# FMC_DIO_32ch_lvds_a.net
KiCad netlist of a schematic drawn in Altium Designer
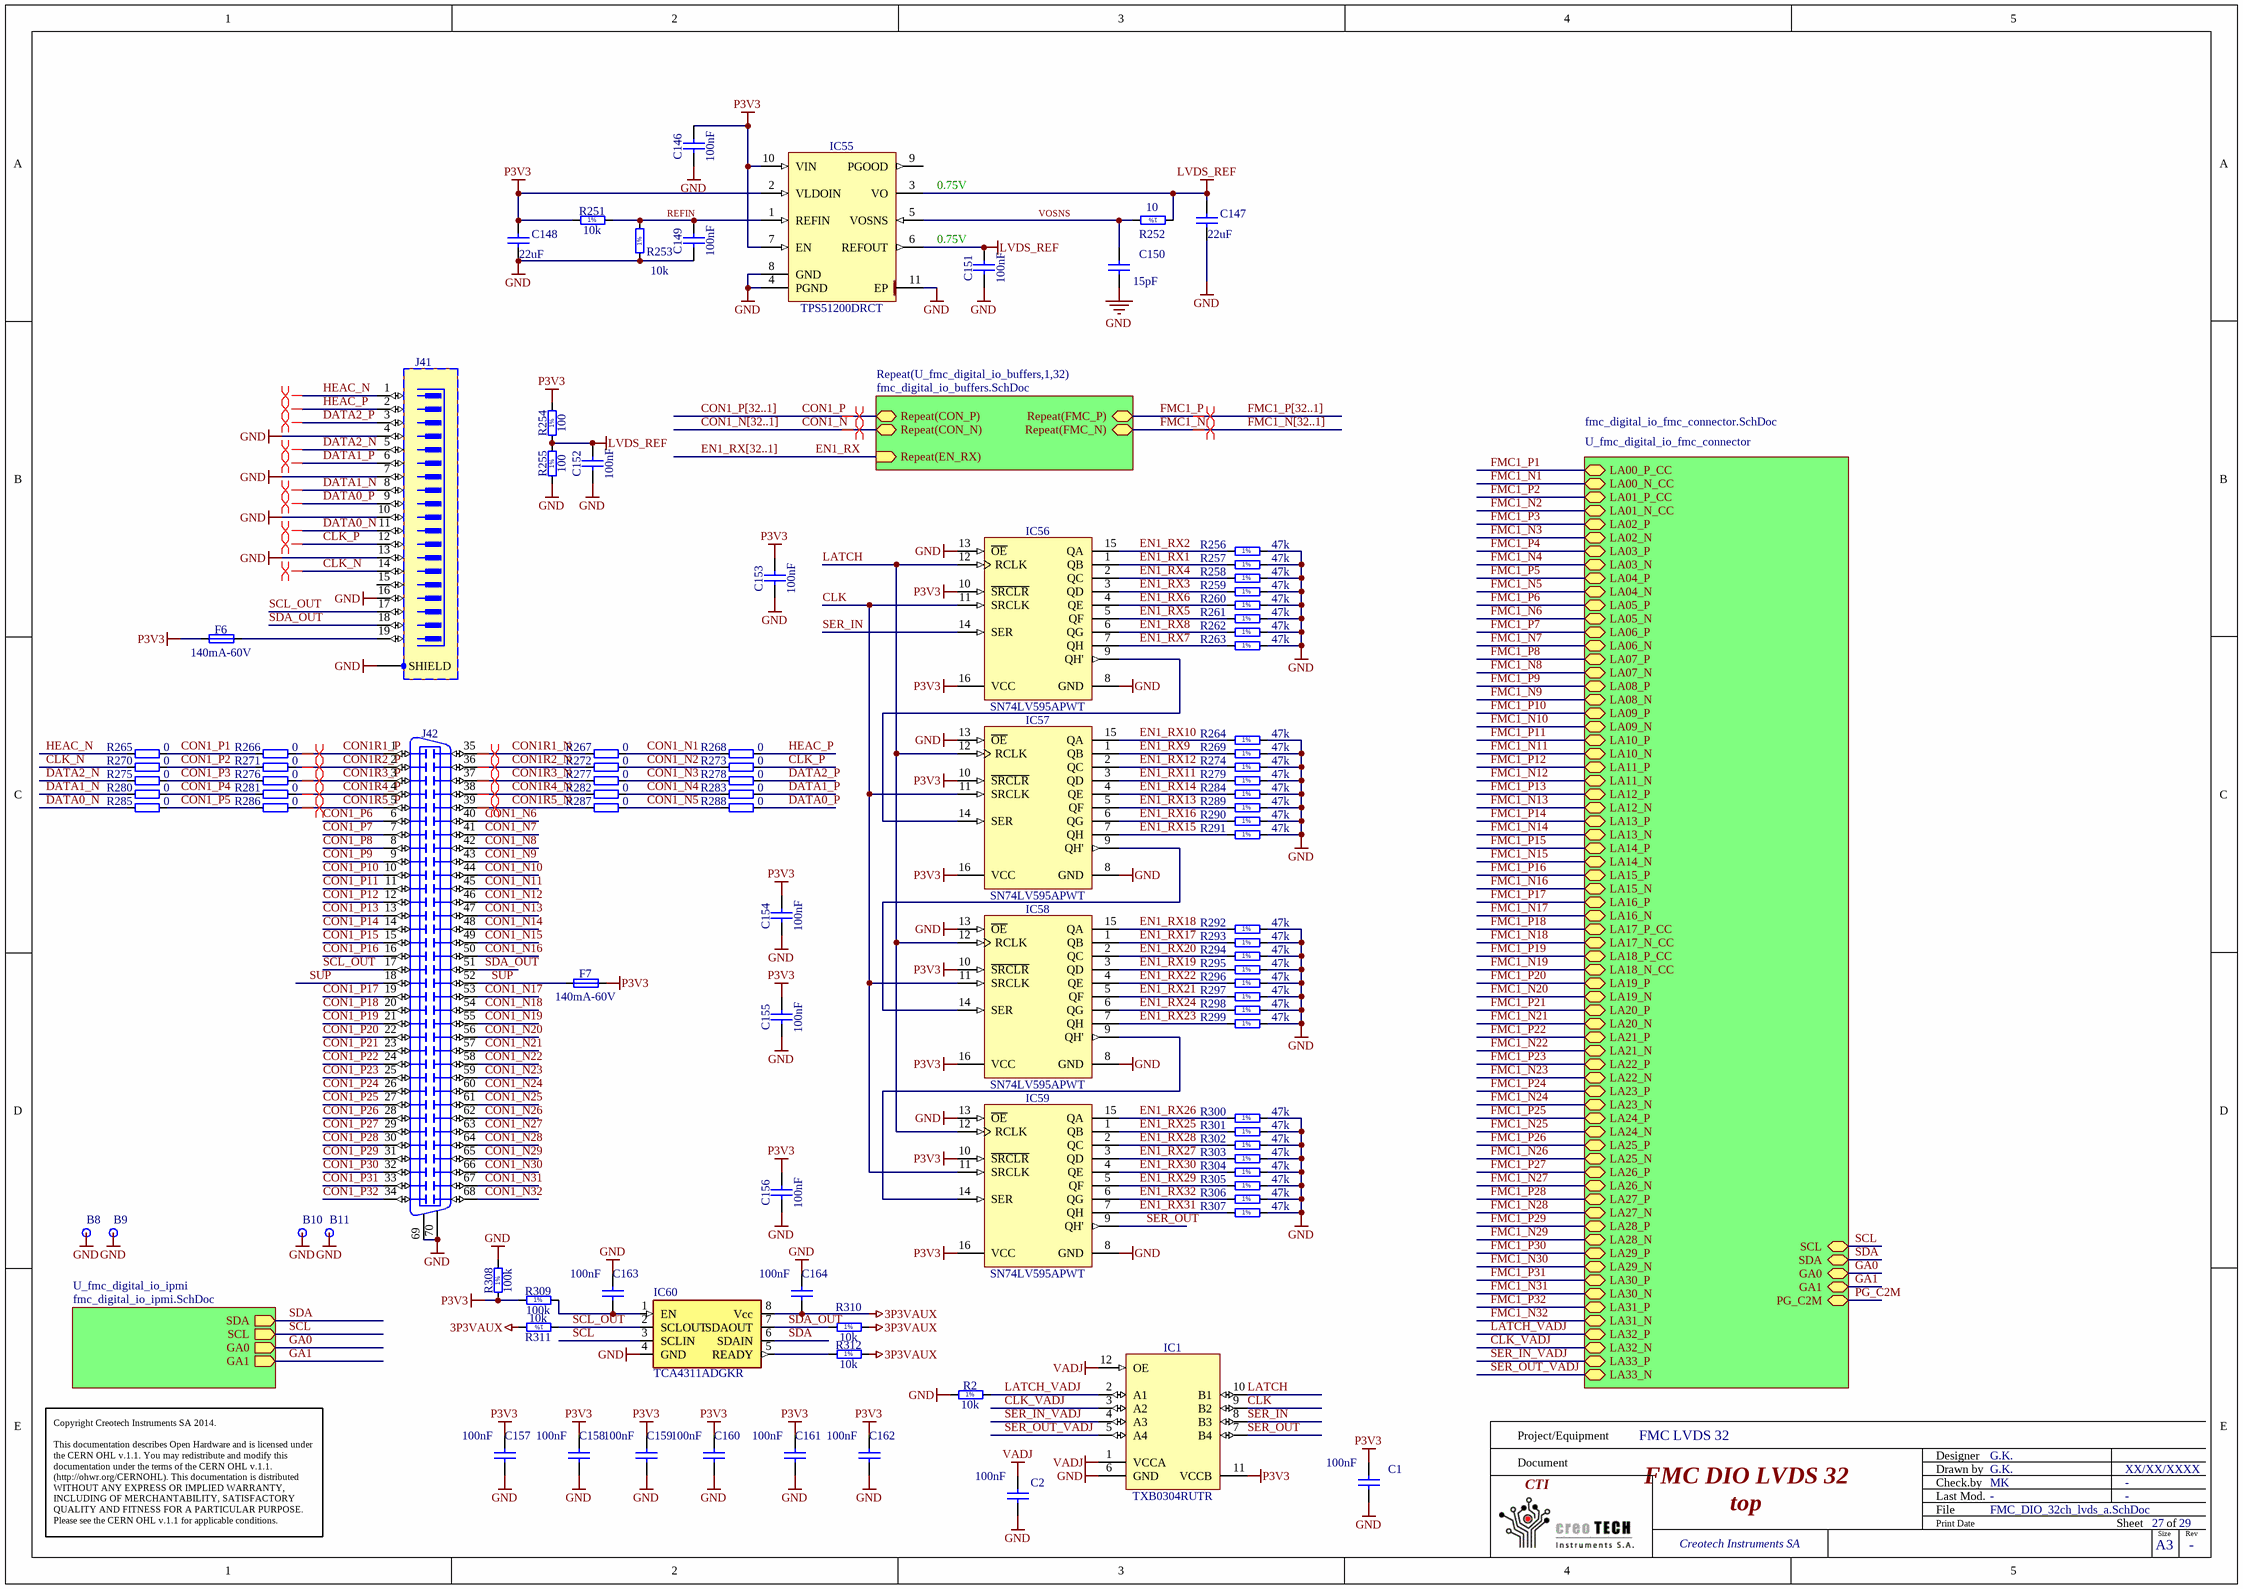
[diagram p0: FMC_DIO_32ch_lvds_a.SchDoc]

(export (version "E")
  (design (tool "Eeschema 10.0.6"))
  (components
    (comp (ref "B8")
      (value "Plated Hole")
      (footprint "MTG300_600")
      (description "Single Terminal Socket")
      (fields (field (name "PART NUMBER") "PLATED_HOLE3.0_PAD6.0") (field (name "AUTHOR") "CERN DEM JLC"))
      (libsource (lib "Eletro-mechanical") (part "Single Terminal Socket"))
    )
    (comp (ref "B9")
      (value "Plated Hole")
      (footprint "MTG300_600")
      (description "Single Terminal Socket")
      (fields (field (name "PART NUMBER") "PLATED_HOLE3.0_PAD6.0") (field (name "AUTHOR") "CERN DEM JLC"))
      (libsource (lib "Eletro-mechanical") (part "Single Terminal Socket"))
    )
    (comp (ref "B10")
      (value "Plated Hole")
      (footprint "MTG300_600")
      (description "Single Terminal Socket")
      (fields (field (name "PART NUMBER") "PLATED_HOLE3.0_PAD6.0") (field (name "AUTHOR") "CERN DEM JLC"))
      (libsource (lib "Eletro-mechanical") (part "Single Terminal Socket"))
    )
    (comp (ref "B11")
      (value "Plated Hole")
      (footprint "MTG300_600")
      (description "Single Terminal Socket")
      (fields (field (name "PART NUMBER") "PLATED_HOLE3.0_PAD6.0") (field (name "AUTHOR") "CERN DEM JLC"))
      (libsource (lib "Eletro-mechanical") (part "Single Terminal Socket"))
    )
    (comp (ref "C1")
      (value "100nF")
      (footprint "CAPC1005X55N")
      (description "Non-polarised capacitor")
      (fields
        (field (name "PART NUMBER") "CC0402_100NF_16V_10%_X7R")
        (field (name "VOLTAGE") "16V")
        (field (name "AUTHOR") "CERN DEM JLC")
      )
      (libsource (lib "Capacitors") (part "Capacitor - non polarized"))
    )
    (comp (ref "C2")
      (value "100nF")
      (footprint "CAPC1005X55N")
      (description "Non-polarised capacitor")
      (fields
        (field (name "PART NUMBER") "CC0402_100NF_16V_10%_X7R")
        (field (name "VOLTAGE") "16V")
        (field (name "AUTHOR") "CERN DEM JLC")
      )
      (libsource (lib "Capacitors") (part "Capacitor - non polarized"))
    )
    (comp (ref "C146")
      (value "100nF")
      (footprint "CAPC1005X55N")
      (description "Non-polarised capacitor")
      (fields
        (field (name "PART NUMBER") "CC0402_100NF_16V_10%_X5R")
        (field (name "VOLTAGE") "16V")
        (field (name "AUTHOR") "CERN DEM JLC")
      )
      (libsource (lib "Capacitors") (part "Capacitor - non polarized"))
    )
    (comp (ref "C147")
      (value "22uF")
      (footprint "CAPC3216X180N")
      (description "Non-polarised capacitor")
      (fields
        (field (name "PART NUMBER") "CC1206_22UF_10V_10%_X7R")
        (field (name "VOLTAGE") "10V")
        (field (name "AUTHOR") "CERN DEM JLC")
      )
      (libsource (lib "Capacitors") (part "Capacitor - non polarized"))
    )
    (comp (ref "C148")
      (value "22uF")
      (footprint "CAPC3216X180N")
      (description "Non-polarised capacitor")
      (fields
        (field (name "PART NUMBER") "CC1206_22UF_10V_10%_X7R")
        (field (name "VOLTAGE") "10V")
        (field (name "AUTHOR") "CERN DEM JLC")
      )
      (libsource (lib "Capacitors") (part "Capacitor - non polarized"))
    )
    (comp (ref "C149")
      (value "100nF")
      (footprint "CAPC1005X55N")
      (description "Non-polarised capacitor")
      (fields
        (field (name "PART NUMBER") "CC0402_100NF_16V_10%_X5R")
        (field (name "VOLTAGE") "16V")
        (field (name "AUTHOR") "CERN DEM JLC")
      )
      (libsource (lib "Capacitors") (part "Capacitor - non polarized"))
    )
    (comp (ref "C150")
      (value "15pF")
      (footprint "CAPC1005X55N")
      (description "Non-polarised capacitor")
      (fields
        (field (name "PART NUMBER") "CC0402_15PF_50V_5%_NP0")
        (field (name "VOLTAGE") "50V")
        (field (name "AUTHOR") "CERN DEM JLC")
      )
      (libsource (lib "Capacitors") (part "Capacitor - non polarized"))
    )
    (comp (ref "C151")
      (value "100nF")
      (footprint "CAPC1005X55N")
      (description "Non-polarised capacitor")
      (fields
        (field (name "PART NUMBER") "CC0402_100NF_16V_10%_X5R")
        (field (name "VOLTAGE") "16V")
        (field (name "AUTHOR") "CERN DEM JLC")
      )
      (libsource (lib "Capacitors") (part "Capacitor - non polarized"))
    )
    (comp (ref "C152")
      (value "100nF")
      (footprint "CAPC1005X55N")
      (description "Non-polarised capacitor")
      (fields
        (field (name "PART NUMBER") "CC0402_100NF_16V_10%_X5R")
        (field (name "VOLTAGE") "16V")
        (field (name "AUTHOR") "CERN DEM JLC")
      )
      (libsource (lib "Capacitors") (part "Capacitor - non polarized"))
    )
    (comp (ref "C153")
      (value "100nF")
      (footprint "CAPC1005X55N")
      (description "Non-polarised capacitor")
      (fields
        (field (name "PART NUMBER") "CC0402_100NF_16V_10%_X5R")
        (field (name "VOLTAGE") "16V")
        (field (name "AUTHOR") "CERN DEM JLC")
      )
      (libsource (lib "Capacitors") (part "Capacitor - non polarized"))
    )
    (comp (ref "C154")
      (value "100nF")
      (footprint "CAPC1005X55N")
      (description "Non-polarised capacitor")
      (fields
        (field (name "PART NUMBER") "CC0402_100NF_16V_10%_X5R")
        (field (name "VOLTAGE") "16V")
        (field (name "AUTHOR") "CERN DEM JLC")
      )
      (libsource (lib "Capacitors") (part "Capacitor - non polarized"))
    )
    (comp (ref "C155")
      (value "100nF")
      (footprint "CAPC1005X55N")
      (description "Non-polarised capacitor")
      (fields
        (field (name "PART NUMBER") "CC0402_100NF_16V_10%_X5R")
        (field (name "VOLTAGE") "16V")
        (field (name "AUTHOR") "CERN DEM JLC")
      )
      (libsource (lib "Capacitors") (part "Capacitor - non polarized"))
    )
    (comp (ref "C156")
      (value "100nF")
      (footprint "CAPC1005X55N")
      (description "Non-polarised capacitor")
      (fields
        (field (name "PART NUMBER") "CC0402_100NF_16V_10%_X5R")
        (field (name "VOLTAGE") "16V")
        (field (name "AUTHOR") "CERN DEM JLC")
      )
      (libsource (lib "Capacitors") (part "Capacitor - non polarized"))
    )
    (comp (ref "C157")
      (value "100nF")
      (footprint "CAPC1005X55N")
      (description "Non-polarised capacitor")
      (fields
        (field (name "PART NUMBER") "CC0402_100NF_16V_10%_X7R")
        (field (name "VOLTAGE") "16V")
        (field (name "AUTHOR") "CERN DEM JLC")
      )
      (libsource (lib "Capacitors") (part "Capacitor - non polarized"))
    )
    (comp (ref "C158")
      (value "100nF")
      (footprint "CAPC1005X55N")
      (description "Non-polarised capacitor")
      (fields
        (field (name "PART NUMBER") "CC0402_100NF_16V_10%_X7R")
        (field (name "VOLTAGE") "16V")
        (field (name "AUTHOR") "CERN DEM JLC")
      )
      (libsource (lib "Capacitors") (part "Capacitor - non polarized"))
    )
    (comp (ref "C159")
      (value "100nF")
      (footprint "CAPC1005X55N")
      (description "Non-polarised capacitor")
      (fields
        (field (name "PART NUMBER") "CC0402_100NF_16V_10%_X7R")
        (field (name "VOLTAGE") "16V")
        (field (name "AUTHOR") "CERN DEM JLC")
      )
      (libsource (lib "Capacitors") (part "Capacitor - non polarized"))
    )
    (comp (ref "C160")
      (value "100nF")
      (footprint "CAPC1005X55N")
      (description "Non-polarised capacitor")
      (fields
        (field (name "PART NUMBER") "CC0402_100NF_16V_10%_X7R")
        (field (name "VOLTAGE") "16V")
        (field (name "AUTHOR") "CERN DEM JLC")
      )
      (libsource (lib "Capacitors") (part "Capacitor - non polarized"))
    )
    (comp (ref "C161")
      (value "100nF")
      (footprint "CAPC1005X55N")
      (description "Non-polarised capacitor")
      (fields
        (field (name "PART NUMBER") "CC0402_100NF_16V_10%_X7R")
        (field (name "VOLTAGE") "16V")
        (field (name "AUTHOR") "CERN DEM JLC")
      )
      (libsource (lib "Capacitors") (part "Capacitor - non polarized"))
    )
    (comp (ref "C162")
      (value "100nF")
      (footprint "CAPC1005X55N")
      (description "Non-polarised capacitor")
      (fields
        (field (name "PART NUMBER") "CC0402_100NF_16V_10%_X7R")
        (field (name "VOLTAGE") "16V")
        (field (name "AUTHOR") "CERN DEM JLC")
      )
      (libsource (lib "Capacitors") (part "Capacitor - non polarized"))
    )
    (comp (ref "C163")
      (value "100nF")
      (footprint "CAPC1005X55N")
      (description "Non-polarised capacitor")
      (fields
        (field (name "PART NUMBER") "CC0402_100NF_16V_10%_X7R")
        (field (name "VOLTAGE") "16V")
        (field (name "AUTHOR") "CERN DEM JLC")
      )
      (libsource (lib "Capacitors") (part "Capacitor - non polarized"))
    )
    (comp (ref "C164")
      (value "100nF")
      (footprint "CAPC1005X55N")
      (description "Non-polarised capacitor")
      (fields
        (field (name "PART NUMBER") "CC0402_100NF_16V_10%_X7R")
        (field (name "VOLTAGE") "16V")
        (field (name "AUTHOR") "CERN DEM JLC")
      )
      (libsource (lib "Capacitors") (part "Capacitor - non polarized"))
    )
    (comp (ref "F6")
      (value "140mA-60V")
      (footprint "FUSRC4632X90N")
      (description "Fuse")
      (fields
        (field (name "PART NUMBER") "FUSR1812_TYCO-MINISMDC014F")
        (field (name "MANUFACTURER") "TYCO ELECTRONICS")
        (field (name "AUTHOR") "CERN DEM JLC")
      )
      (libsource (lib "Eletro-mechanical") (part "Fuse"))
    )
    (comp (ref "F7")
      (value "140mA-60V")
      (footprint "FUSRC4632X90N")
      (description "Fuse")
      (fields
        (field (name "PART NUMBER") "FUSR1812_TYCO-MINISMDC014F")
        (field (name "MANUFACTURER") "TYCO ELECTRONICS")
        (field (name "AUTHOR") "CERN DEM JLC")
      )
      (libsource (lib "Eletro-mechanical") (part "Fuse"))
    )
    (comp (ref "IC1")
      (value "TXB0304RUTR")
      (footprint "TEXAS_RUT (R-PUQFN-N12)")
      (description "4-bit Bidirectional Auto-direction Sensing Translator with Fully Symmetric 0.9V to 3.6V Range")
      (fields (field (name "MANUFACTURER") "TEXAS INSTRUMENTS") (field (name "AUTHOR") "CERN DEM JLC"))
      (libsource (lib "ICs And Semiconductors") (part "TXB0304RUTR"))
    )
    (comp (ref "IC55")
      (value "TPS51200DRCT")
      (footprint "TEXAS_DRC (S-PVSON-N10)")
      (description "Sink/Source DDR Termination Regulator")
      (fields (field (name "MANUFACTURER") "TEXAS INSTRUMENTS") (field (name "AUTHOR") "CERN DEM JLC"))
      (libsource (lib "ICs And Semiconductors") (part "TPS51200DRC"))
    )
    (comp (ref "IC56")
      (value "SN74LV595APWT")
      (footprint "SOP65P640X120-16N")
      (description "8-Bit Shift Register With 3-State Output Register")
      (fields (field (name "MANUFACTURER") "TEXAS INSTRUMENTS") (field (name "AUTHOR") "CERN DEM JLC"))
      (libsource (lib "ICs And Semiconductors") (part "74595"))
    )
    (comp (ref "IC57")
      (value "SN74LV595APWT")
      (footprint "SOP65P640X120-16N")
      (description "8-Bit Shift Register With 3-State Output Register")
      (fields (field (name "MANUFACTURER") "TEXAS INSTRUMENTS") (field (name "AUTHOR") "CERN DEM JLC"))
      (libsource (lib "ICs And Semiconductors") (part "74595"))
    )
    (comp (ref "IC58")
      (value "SN74LV595APWT")
      (footprint "SOP65P640X120-16N")
      (description "8-Bit Shift Register With 3-State Output Register")
      (fields (field (name "MANUFACTURER") "TEXAS INSTRUMENTS") (field (name "AUTHOR") "CERN DEM JLC"))
      (libsource (lib "ICs And Semiconductors") (part "74595"))
    )
    (comp (ref "IC59")
      (value "SN74LV595APWT")
      (footprint "SOP65P640X120-16N")
      (description "8-Bit Shift Register With 3-State Output Register")
      (fields (field (name "MANUFACTURER") "TEXAS INSTRUMENTS") (field (name "AUTHOR") "CERN DEM JLC"))
      (libsource (lib "ICs And Semiconductors") (part "74595"))
    )
    (comp (ref "IC60")
      (value "TCA4311ADGKR")
      (footprint "msop-8")
      (description "HOT SWAPPABLE 2-WIRE BUS BUFFERS")
      (libsource (lib "LIBRARY_SCH") (part "IIC_TCA4311A"))
    )
    (comp (ref "J41")
      (value "HDMI")
      (footprint "MOLEX_46765-1001")
      (description "Connector HDMI 19 Male + 1 Shield")
      (fields
        (field (name "PART NUMBER") "MOLEX_46765-1001")
        (field (name "MANUFACTURER") "MOLEX")
        (field (name "AUTHOR") "CERN DEM JLC")
      )
      (libsource (lib "Connectors") (part "Connector HDMI 19 Male + 1 Shield"))
    )
    (comp (ref "J42")
      (value "DNP")
      (footprint "MOLEX_71430-0013")
      (description "Very High Density Cable Interconnect (VHDCI ) 68 Female")
      (fields
        (field (name "PART NUMBER") "MOLEX_71430-0013")
        (field (name "MANUFACTURER") "MOLEX")
        (field (name "AUTHOR") "CERN DEM JLC")
      )
      (libsource (lib "Connectors") (part "Connector VHDCI 68 Female"))
    )
    (comp (ref "R2")
      (value "10k")
      (footprint "RESC1005X40N")
      (description "Resistor - 1%")
      (fields
        (field (name "PART NUMBER") "R0402_10K_1%_0.0625W_100PPM")
        (field (name "POWER") "0.0625W")
        (field (name "AUTHOR") "CERN DEM JLC")
      )
      (libsource (lib "Resistors") (part "Resistor - 1%"))
    )
    (comp (ref "R251")
      (value "10k")
      (footprint "RESC1005X40N")
      (description "Resistor - 1%")
      (fields
        (field (name "PART NUMBER") "R0402_10K_1%_0.0625W_100PPM")
        (field (name "POWER") "0.0625W")
        (field (name "AUTHOR") "CERN DEM JLC")
      )
      (libsource (lib "Resistors") (part "Resistor - 1%"))
    )
    (comp (ref "R252")
      (value "10")
      (footprint "RESC1005X40N")
      (description "Resistor - 1%")
      (fields
        (field (name "PART NUMBER") "R0402_10R_1%_0.0625W_200PPM")
        (field (name "POWER") "0.0625W")
        (field (name "AUTHOR") "CERN DEM JLC")
      )
      (libsource (lib "Resistors") (part "Resistor - 1%"))
    )
    (comp (ref "R253")
      (value "10k")
      (footprint "RESC1005X40N")
      (description "Resistor - 1%")
      (fields
        (field (name "PART NUMBER") "R0402_10K_1%_0.0625W_100PPM")
        (field (name "POWER") "0.0625W")
        (field (name "AUTHOR") "CERN DEM JLC")
      )
      (libsource (lib "Resistors") (part "Resistor - 1%"))
    )
    (comp (ref "R254")
      (value "100")
      (footprint "RESC1005X40N")
      (description "Resistor - 1%")
      (fields
        (field (name "PART NUMBER") "R0402_100R_1%_0.0625W_100PPM")
        (field (name "POWER") "0.0625W")
        (field (name "AUTHOR") "CERN DEM JLC")
      )
      (libsource (lib "Resistors") (part "Resistor - 1%"))
    )
    (comp (ref "R255")
      (value "100")
      (footprint "RESC1005X40N")
      (description "Resistor - 1%")
      (fields
        (field (name "PART NUMBER") "R0402_100R_1%_0.0625W_100PPM")
        (field (name "POWER") "0.0625W")
        (field (name "AUTHOR") "CERN DEM JLC")
      )
      (libsource (lib "Resistors") (part "Resistor - 1%"))
    )
    (comp (ref "R256")
      (value "47k")
      (footprint "RESC1005X40N")
      (description "Resistor - 1%")
      (fields
        (field (name "PART NUMBER") "R0402_47K_1%_0.0625W_100PPM")
        (field (name "POWER") "0.0625W")
        (field (name "AUTHOR") "CERN DEM JLC")
      )
      (libsource (lib "Resistors") (part "Resistor - 1%"))
    )
    (comp (ref "R257")
      (value "47k")
      (footprint "RESC1005X40N")
      (description "Resistor - 1%")
      (fields
        (field (name "PART NUMBER") "R0402_47K_1%_0.0625W_100PPM")
        (field (name "POWER") "0.0625W")
        (field (name "AUTHOR") "CERN DEM JLC")
      )
      (libsource (lib "Resistors") (part "Resistor - 1%"))
    )
    (comp (ref "R258")
      (value "47k")
      (footprint "RESC1005X40N")
      (description "Resistor - 1%")
      (fields
        (field (name "PART NUMBER") "R0402_47K_1%_0.0625W_100PPM")
        (field (name "POWER") "0.0625W")
        (field (name "AUTHOR") "CERN DEM JLC")
      )
      (libsource (lib "Resistors") (part "Resistor - 1%"))
    )
    (comp (ref "R259")
      (value "47k")
      (footprint "RESC1005X40N")
      (description "Resistor - 1%")
      (fields
        (field (name "PART NUMBER") "R0402_47K_1%_0.0625W_100PPM")
        (field (name "POWER") "0.0625W")
        (field (name "AUTHOR") "CERN DEM JLC")
      )
      (libsource (lib "Resistors") (part "Resistor - 1%"))
    )
    (comp (ref "R260")
      (value "47k")
      (footprint "RESC1005X40N")
      (description "Resistor - 1%")
      (fields
        (field (name "PART NUMBER") "R0402_47K_1%_0.0625W_100PPM")
        (field (name "POWER") "0.0625W")
        (field (name "AUTHOR") "CERN DEM JLC")
      )
      (libsource (lib "Resistors") (part "Resistor - 1%"))
    )
    (comp (ref "R261")
      (value "47k")
      (footprint "RESC1005X40N")
      (description "Resistor - 1%")
      (fields
        (field (name "PART NUMBER") "R0402_47K_1%_0.0625W_100PPM")
        (field (name "POWER") "0.0625W")
        (field (name "AUTHOR") "CERN DEM JLC")
      )
      (libsource (lib "Resistors") (part "Resistor - 1%"))
    )
    (comp (ref "R262")
      (value "47k")
      (footprint "RESC1005X40N")
      (description "Resistor - 1%")
      (fields
        (field (name "PART NUMBER") "R0402_47K_1%_0.0625W_100PPM")
        (field (name "POWER") "0.0625W")
        (field (name "AUTHOR") "CERN DEM JLC")
      )
      (libsource (lib "Resistors") (part "Resistor - 1%"))
    )
    (comp (ref "R263")
      (value "47k")
      (footprint "RESC1005X40N")
      (description "Resistor - 1%")
      (fields
        (field (name "PART NUMBER") "R0402_47K_1%_0.0625W_100PPM")
        (field (name "POWER") "0.0625W")
        (field (name "AUTHOR") "CERN DEM JLC")
      )
      (libsource (lib "Resistors") (part "Resistor - 1%"))
    )
    (comp (ref "R264")
      (value "47k")
      (footprint "RESC1005X40N")
      (description "Resistor - 1%")
      (fields
        (field (name "PART NUMBER") "R0402_47K_1%_0.0625W_100PPM")
        (field (name "POWER") "0.0625W")
        (field (name "AUTHOR") "CERN DEM JLC")
      )
      (libsource (lib "Resistors") (part "Resistor - 1%"))
    )
    (comp (ref "R265")
      (value "0")
      (footprint "RESC1005X40N")
      (description "Resistor")
      (fields
        (field (name "PART NUMBER") "R0402_0R_JUMPER")
        (field (name "MANUFACTURER") "GENERIC")
        (field (name "AUTHOR") "CERN DEM JLC")
      )
      (libsource (lib "Resistors") (part "Resistor"))
    )
    (comp (ref "R266")
      (value "0")
      (footprint "RESC1005X40N")
      (description "Resistor")
      (fields
        (field (name "PART NUMBER") "R0402_0R_JUMPER")
        (field (name "MANUFACTURER") "GENERIC")
        (field (name "AUTHOR") "CERN DEM JLC")
      )
      (libsource (lib "Resistors") (part "Resistor"))
    )
    (comp (ref "R267")
      (value "0")
      (footprint "RESC1005X40N")
      (description "Resistor")
      (fields
        (field (name "PART NUMBER") "R0402_0R_JUMPER")
        (field (name "MANUFACTURER") "GENERIC")
        (field (name "AUTHOR") "CERN DEM JLC")
      )
      (libsource (lib "Resistors") (part "Resistor"))
    )
    (comp (ref "R268")
      (value "0")
      (footprint "RESC1005X40N")
      (description "Resistor")
      (fields
        (field (name "PART NUMBER") "R0402_0R_JUMPER")
        (field (name "MANUFACTURER") "GENERIC")
        (field (name "AUTHOR") "CERN DEM JLC")
      )
      (libsource (lib "Resistors") (part "Resistor"))
    )
    (comp (ref "R269")
      (value "47k")
      (footprint "RESC1005X40N")
      (description "Resistor - 1%")
      (fields
        (field (name "PART NUMBER") "R0402_47K_1%_0.0625W_100PPM")
        (field (name "POWER") "0.0625W")
        (field (name "AUTHOR") "CERN DEM JLC")
      )
      (libsource (lib "Resistors") (part "Resistor - 1%"))
    )
    (comp (ref "R270")
      (value "0")
      (footprint "RESC1005X40N")
      (description "Resistor")
      (fields
        (field (name "PART NUMBER") "R0402_0R_JUMPER")
        (field (name "MANUFACTURER") "GENERIC")
        (field (name "AUTHOR") "CERN DEM JLC")
      )
      (libsource (lib "Resistors") (part "Resistor"))
    )
    (comp (ref "R271")
      (value "0")
      (footprint "RESC1005X40N")
      (description "Resistor")
      (fields
        (field (name "PART NUMBER") "R0402_0R_JUMPER")
        (field (name "MANUFACTURER") "GENERIC")
        (field (name "AUTHOR") "CERN DEM JLC")
      )
      (libsource (lib "Resistors") (part "Resistor"))
    )
    (comp (ref "R272")
      (value "0")
      (footprint "RESC1005X40N")
      (description "Resistor")
      (fields
        (field (name "PART NUMBER") "R0402_0R_JUMPER")
        (field (name "MANUFACTURER") "GENERIC")
        (field (name "AUTHOR") "CERN DEM JLC")
      )
      (libsource (lib "Resistors") (part "Resistor"))
    )
    (comp (ref "R273")
      (value "0")
      (footprint "RESC1005X40N")
      (description "Resistor")
      (fields
        (field (name "PART NUMBER") "R0402_0R_JUMPER")
        (field (name "MANUFACTURER") "GENERIC")
        (field (name "AUTHOR") "CERN DEM JLC")
      )
      (libsource (lib "Resistors") (part "Resistor"))
    )
    (comp (ref "R274")
      (value "47k")
      (footprint "RESC1005X40N")
      (description "Resistor - 1%")
      (fields
        (field (name "PART NUMBER") "R0402_47K_1%_0.0625W_100PPM")
        (field (name "POWER") "0.0625W")
        (field (name "AUTHOR") "CERN DEM JLC")
      )
      (libsource (lib "Resistors") (part "Resistor - 1%"))
    )
    (comp (ref "R275")
      (value "0")
      (footprint "RESC1005X40N")
      (description "Resistor")
      (fields
        (field (name "PART NUMBER") "R0402_0R_JUMPER")
        (field (name "MANUFACTURER") "GENERIC")
        (field (name "AUTHOR") "CERN DEM JLC")
      )
      (libsource (lib "Resistors") (part "Resistor"))
    )
    (comp (ref "R276")
      (value "0")
      (footprint "RESC1005X40N")
      (description "Resistor")
      (fields
        (field (name "PART NUMBER") "R0402_0R_JUMPER")
        (field (name "MANUFACTURER") "GENERIC")
        (field (name "AUTHOR") "CERN DEM JLC")
      )
      (libsource (lib "Resistors") (part "Resistor"))
    )
    (comp (ref "R277")
      (value "0")
      (footprint "RESC1005X40N")
      (description "Resistor")
      (fields
        (field (name "PART NUMBER") "R0402_0R_JUMPER")
        (field (name "MANUFACTURER") "GENERIC")
        (field (name "AUTHOR") "CERN DEM JLC")
      )
      (libsource (lib "Resistors") (part "Resistor"))
    )
    (comp (ref "R278")
      (value "0")
      (footprint "RESC1005X40N")
      (description "Resistor")
      (fields
        (field (name "PART NUMBER") "R0402_0R_JUMPER")
        (field (name "MANUFACTURER") "GENERIC")
        (field (name "AUTHOR") "CERN DEM JLC")
      )
      (libsource (lib "Resistors") (part "Resistor"))
    )
    (comp (ref "R279")
      (value "47k")
      (footprint "RESC1005X40N")
      (description "Resistor - 1%")
      (fields
        (field (name "PART NUMBER") "R0402_47K_1%_0.0625W_100PPM")
        (field (name "POWER") "0.0625W")
        (field (name "AUTHOR") "CERN DEM JLC")
      )
      (libsource (lib "Resistors") (part "Resistor - 1%"))
    )
    (comp (ref "R280")
      (value "0")
      (footprint "RESC1005X40N")
      (description "Resistor")
      (fields
        (field (name "PART NUMBER") "R0402_0R_JUMPER")
        (field (name "MANUFACTURER") "GENERIC")
        (field (name "AUTHOR") "CERN DEM JLC")
      )
      (libsource (lib "Resistors") (part "Resistor"))
    )
    (comp (ref "R281")
      (value "0")
      (footprint "RESC1005X40N")
      (description "Resistor")
      (fields
        (field (name "PART NUMBER") "R0402_0R_JUMPER")
        (field (name "MANUFACTURER") "GENERIC")
        (field (name "AUTHOR") "CERN DEM JLC")
      )
      (libsource (lib "Resistors") (part "Resistor"))
    )
    (comp (ref "R282")
      (value "0")
      (footprint "RESC1005X40N")
      (description "Resistor")
      (fields
        (field (name "PART NUMBER") "R0402_0R_JUMPER")
        (field (name "MANUFACTURER") "GENERIC")
        (field (name "AUTHOR") "CERN DEM JLC")
      )
      (libsource (lib "Resistors") (part "Resistor"))
    )
    (comp (ref "R283")
      (value "0")
      (footprint "RESC1005X40N")
      (description "Resistor")
      (fields
        (field (name "PART NUMBER") "R0402_0R_JUMPER")
        (field (name "MANUFACTURER") "GENERIC")
        (field (name "AUTHOR") "CERN DEM JLC")
      )
      (libsource (lib "Resistors") (part "Resistor"))
    )
    (comp (ref "R284")
      (value "47k")
      (footprint "RESC1005X40N")
      (description "Resistor - 1%")
      (fields
        (field (name "PART NUMBER") "R0402_47K_1%_0.0625W_100PPM")
        (field (name "POWER") "0.0625W")
        (field (name "AUTHOR") "CERN DEM JLC")
      )
      (libsource (lib "Resistors") (part "Resistor - 1%"))
    )
    (comp (ref "R285")
      (value "0")
      (footprint "RESC1005X40N")
      (description "Resistor")
      (fields
        (field (name "PART NUMBER") "R0402_0R_JUMPER")
        (field (name "MANUFACTURER") "GENERIC")
        (field (name "AUTHOR") "CERN DEM JLC")
      )
      (libsource (lib "Resistors") (part "Resistor"))
    )
    (comp (ref "R286")
      (value "0")
      (footprint "RESC1005X40N")
      (description "Resistor")
      (fields
        (field (name "PART NUMBER") "R0402_0R_JUMPER")
        (field (name "MANUFACTURER") "GENERIC")
        (field (name "AUTHOR") "CERN DEM JLC")
      )
      (libsource (lib "Resistors") (part "Resistor"))
    )
    (comp (ref "R287")
      (value "0")
      (footprint "RESC1005X40N")
      (description "Resistor")
      (fields
        (field (name "PART NUMBER") "R0402_0R_JUMPER")
        (field (name "MANUFACTURER") "GENERIC")
        (field (name "AUTHOR") "CERN DEM JLC")
      )
      (libsource (lib "Resistors") (part "Resistor"))
    )
    (comp (ref "R288")
      (value "0")
      (footprint "RESC1005X40N")
      (description "Resistor")
      (fields
        (field (name "PART NUMBER") "R0402_0R_JUMPER")
        (field (name "MANUFACTURER") "GENERIC")
        (field (name "AUTHOR") "CERN DEM JLC")
      )
      (libsource (lib "Resistors") (part "Resistor"))
    )
    (comp (ref "R289")
      (value "47k")
      (footprint "RESC1005X40N")
      (description "Resistor - 1%")
      (fields
        (field (name "PART NUMBER") "R0402_47K_1%_0.0625W_100PPM")
        (field (name "POWER") "0.0625W")
        (field (name "AUTHOR") "CERN DEM JLC")
      )
      (libsource (lib "Resistors") (part "Resistor - 1%"))
    )
    (comp (ref "R290")
      (value "47k")
      (footprint "RESC1005X40N")
      (description "Resistor - 1%")
      (fields
        (field (name "PART NUMBER") "R0402_47K_1%_0.0625W_100PPM")
        (field (name "POWER") "0.0625W")
        (field (name "AUTHOR") "CERN DEM JLC")
      )
      (libsource (lib "Resistors") (part "Resistor - 1%"))
    )
    (comp (ref "R291")
      (value "47k")
      (footprint "RESC1005X40N")
      (description "Resistor - 1%")
      (fields
        (field (name "PART NUMBER") "R0402_47K_1%_0.0625W_100PPM")
        (field (name "POWER") "0.0625W")
        (field (name "AUTHOR") "CERN DEM JLC")
      )
      (libsource (lib "Resistors") (part "Resistor - 1%"))
    )
    (comp (ref "R292")
      (value "47k")
      (footprint "RESC1005X40N")
      (description "Resistor - 1%")
      (fields
        (field (name "PART NUMBER") "R0402_47K_1%_0.0625W_100PPM")
        (field (name "POWER") "0.0625W")
        (field (name "AUTHOR") "CERN DEM JLC")
      )
      (libsource (lib "Resistors") (part "Resistor - 1%"))
    )
    (comp (ref "R293")
      (value "47k")
      (footprint "RESC1005X40N")
      (description "Resistor - 1%")
      (fields
        (field (name "PART NUMBER") "R0402_47K_1%_0.0625W_100PPM")
        (field (name "POWER") "0.0625W")
        (field (name "AUTHOR") "CERN DEM JLC")
      )
      (libsource (lib "Resistors") (part "Resistor - 1%"))
    )
    (comp (ref "R294")
      (value "47k")
      (footprint "RESC1005X40N")
      (description "Resistor - 1%")
      (fields
        (field (name "PART NUMBER") "R0402_47K_1%_0.0625W_100PPM")
        (field (name "POWER") "0.0625W")
        (field (name "AUTHOR") "CERN DEM JLC")
      )
      (libsource (lib "Resistors") (part "Resistor - 1%"))
    )
    (comp (ref "R295")
      (value "47k")
      (footprint "RESC1005X40N")
      (description "Resistor - 1%")
      (fields
        (field (name "PART NUMBER") "R0402_47K_1%_0.0625W_100PPM")
        (field (name "POWER") "0.0625W")
        (field (name "AUTHOR") "CERN DEM JLC")
      )
      (libsource (lib "Resistors") (part "Resistor - 1%"))
    )
    (comp (ref "R296")
      (value "47k")
      (footprint "RESC1005X40N")
      (description "Resistor - 1%")
      (fields
        (field (name "PART NUMBER") "R0402_47K_1%_0.0625W_100PPM")
        (field (name "POWER") "0.0625W")
        (field (name "AUTHOR") "CERN DEM JLC")
      )
      (libsource (lib "Resistors") (part "Resistor - 1%"))
    )
    (comp (ref "R297")
      (value "47k")
      (footprint "RESC1005X40N")
      (description "Resistor - 1%")
      (fields
        (field (name "PART NUMBER") "R0402_47K_1%_0.0625W_100PPM")
        (field (name "POWER") "0.0625W")
        (field (name "AUTHOR") "CERN DEM JLC")
      )
      (libsource (lib "Resistors") (part "Resistor - 1%"))
    )
    (comp (ref "R298")
      (value "47k")
      (footprint "RESC1005X40N")
      (description "Resistor - 1%")
      (fields
        (field (name "PART NUMBER") "R0402_47K_1%_0.0625W_100PPM")
        (field (name "POWER") "0.0625W")
        (field (name "AUTHOR") "CERN DEM JLC")
      )
      (libsource (lib "Resistors") (part "Resistor - 1%"))
    )
    (comp (ref "R299")
      (value "47k")
      (footprint "RESC1005X40N")
      (description "Resistor - 1%")
      (fields
        (field (name "PART NUMBER") "R0402_47K_1%_0.0625W_100PPM")
        (field (name "POWER") "0.0625W")
        (field (name "AUTHOR") "CERN DEM JLC")
      )
      (libsource (lib "Resistors") (part "Resistor - 1%"))
    )
    (comp (ref "R300")
      (value "47k")
      (footprint "RESC1005X40N")
      (description "Resistor - 1%")
      (fields
        (field (name "PART NUMBER") "R0402_47K_1%_0.0625W_100PPM")
        (field (name "POWER") "0.0625W")
        (field (name "AUTHOR") "CERN DEM JLC")
      )
      (libsource (lib "Resistors") (part "Resistor - 1%"))
    )
    (comp (ref "R301")
      (value "47k")
      (footprint "RESC1005X40N")
      (description "Resistor - 1%")
      (fields
        (field (name "PART NUMBER") "R0402_47K_1%_0.0625W_100PPM")
        (field (name "POWER") "0.0625W")
        (field (name "AUTHOR") "CERN DEM JLC")
      )
      (libsource (lib "Resistors") (part "Resistor - 1%"))
    )
    (comp (ref "R302")
      (value "47k")
      (footprint "RESC1005X40N")
      (description "Resistor - 1%")
      (fields
        (field (name "PART NUMBER") "R0402_47K_1%_0.0625W_100PPM")
        (field (name "POWER") "0.0625W")
        (field (name "AUTHOR") "CERN DEM JLC")
      )
      (libsource (lib "Resistors") (part "Resistor - 1%"))
    )
    (comp (ref "R303")
      (value "47k")
      (footprint "RESC1005X40N")
      (description "Resistor - 1%")
      (fields
        (field (name "PART NUMBER") "R0402_47K_1%_0.0625W_100PPM")
        (field (name "POWER") "0.0625W")
        (field (name "AUTHOR") "CERN DEM JLC")
      )
      (libsource (lib "Resistors") (part "Resistor - 1%"))
    )
    (comp (ref "R304")
      (value "47k")
      (footprint "RESC1005X40N")
      (description "Resistor - 1%")
      (fields
        (field (name "PART NUMBER") "R0402_47K_1%_0.0625W_100PPM")
        (field (name "POWER") "0.0625W")
        (field (name "AUTHOR") "CERN DEM JLC")
      )
      (libsource (lib "Resistors") (part "Resistor - 1%"))
    )
    (comp (ref "R305")
      (value "47k")
      (footprint "RESC1005X40N")
      (description "Resistor - 1%")
      (fields
        (field (name "PART NUMBER") "R0402_47K_1%_0.0625W_100PPM")
        (field (name "POWER") "0.0625W")
        (field (name "AUTHOR") "CERN DEM JLC")
      )
      (libsource (lib "Resistors") (part "Resistor - 1%"))
    )
    (comp (ref "R306")
      (value "47k")
      (footprint "RESC1005X40N")
      (description "Resistor - 1%")
      (fields
        (field (name "PART NUMBER") "R0402_47K_1%_0.0625W_100PPM")
        (field (name "POWER") "0.0625W")
        (field (name "AUTHOR") "CERN DEM JLC")
      )
      (libsource (lib "Resistors") (part "Resistor - 1%"))
    )
    (comp (ref "R307")
      (value "47k")
      (footprint "RESC1005X40N")
      (description "Resistor - 1%")
      (fields
        (field (name "PART NUMBER") "R0402_47K_1%_0.0625W_100PPM")
        (field (name "POWER") "0.0625W")
        (field (name "AUTHOR") "CERN DEM JLC")
      )
      (libsource (lib "Resistors") (part "Resistor - 1%"))
    )
    (comp (ref "R308")
      (value "100k")
      (footprint "RESC1005X40N")
      (description "Resistor - 1%")
      (fields
        (field (name "PART NUMBER") "R0402_100K_1%_0.0625W_100PPM")
        (field (name "POWER") "0.0625W")
        (field (name "AUTHOR") "CERN DEM JLC")
      )
      (libsource (lib "Resistors") (part "Resistor - 1%"))
    )
    (comp (ref "R309")
      (value "100k")
      (footprint "RESC1005X40N")
      (description "Resistor - 1%")
      (fields
        (field (name "PART NUMBER") "R0402_100K_1%_0.0625W_100PPM")
        (field (name "POWER") "0.0625W")
        (field (name "AUTHOR") "CERN DEM JLC")
      )
      (libsource (lib "Resistors") (part "Resistor - 1%"))
    )
    (comp (ref "R310")
      (value "10k")
      (footprint "RESC1005X40N")
      (description "Resistor - 1%")
      (fields
        (field (name "PART NUMBER") "R0402_10K_1%_0.0625W_100PPM")
        (field (name "POWER") "0.0625W")
        (field (name "AUTHOR") "CERN DEM JLC")
      )
      (libsource (lib "Resistors") (part "Resistor - 1%"))
    )
    (comp (ref "R311")
      (value "10k")
      (footprint "RESC1005X40N")
      (description "Resistor - 1%")
      (fields
        (field (name "PART NUMBER") "R0402_10K_1%_0.0625W_100PPM")
        (field (name "POWER") "0.0625W")
        (field (name "AUTHOR") "CERN DEM JLC")
      )
      (libsource (lib "Resistors") (part "Resistor - 1%"))
    )
    (comp (ref "R312")
      (value "10k")
      (footprint "RESC1005X40N")
      (description "Resistor - 1%")
      (fields
        (field (name "PART NUMBER") "R0402_10K_1%_0.0625W_100PPM")
        (field (name "POWER") "0.0625W")
        (field (name "AUTHOR") "CERN DEM JLC")
      )
      (libsource (lib "Resistors") (part "Resistor - 1%"))
    )
  )
  (nets
    (net (code "1") (name "/CLK") (class "Default")
      (node (ref "IC1") (pin "9") (pinfunction "B2_9") (pintype "bidirectional"))
      (node (ref "IC56") (pin "11") (pinfunction "SRCLK_11") (pintype "input"))
      (node (ref "IC57") (pin "11") (pinfunction "SRCLK_11") (pintype "input"))
      (node (ref "IC58") (pin "11") (pinfunction "SRCLK_11") (pintype "input"))
      (node (ref "IC59") (pin "11") (pinfunction "SRCLK_11") (pintype "input"))
    )
    (net (code "2") (name "/CLK_N") (class "Default")
      (node (ref "J41") (pin "14") (pinfunction "14_14") (pintype "bidirectional"))
      (node (ref "R270") (pin "1") (pinfunction "1_1") (pintype "passive"))
    )
    (net (code "3") (name "/CLK_P") (class "Default")
      (node (ref "J41") (pin "12") (pinfunction "12_12") (pintype "bidirectional"))
      (node (ref "R273") (pin "2") (pinfunction "2_2") (pintype "passive"))
    )
    (net (code "4") (name "/CLK_VADJ") (class "Default")
      (node (ref "IC1") (pin "3") (pinfunction "A2_3") (pintype "bidirectional"))
    )
    (net (code "5") (name "/CON1R1_N") (class "Default")
      (node (ref "J42") (pin "35") (pinfunction "35_35") (pintype "bidirectional"))
      (node (ref "R267") (pin "1") (pinfunction "1_1") (pintype "passive"))
    )
    (net (code "6") (name "/CON1R1_P") (class "Default")
      (node (ref "J42") (pin "1") (pinfunction "1_1") (pintype "bidirectional"))
      (node (ref "R266") (pin "2") (pinfunction "2_2") (pintype "passive"))
    )
    (net (code "7") (name "/CON1R2_N") (class "Default")
      (node (ref "J42") (pin "36") (pinfunction "36_36") (pintype "bidirectional"))
      (node (ref "R272") (pin "1") (pinfunction "1_1") (pintype "passive"))
    )
    (net (code "8") (name "/CON1R2_P") (class "Default")
      (node (ref "J42") (pin "2") (pinfunction "2_2") (pintype "bidirectional"))
      (node (ref "R271") (pin "2") (pinfunction "2_2") (pintype "passive"))
    )
    (net (code "9") (name "/CON1R3_N") (class "Default")
      (node (ref "J42") (pin "37") (pinfunction "37_37") (pintype "bidirectional"))
      (node (ref "R277") (pin "1") (pinfunction "1_1") (pintype "passive"))
    )
    (net (code "10") (name "/CON1R3_P") (class "Default")
      (node (ref "J42") (pin "3") (pinfunction "3_3") (pintype "bidirectional"))
      (node (ref "R276") (pin "2") (pinfunction "2_2") (pintype "passive"))
    )
    (net (code "11") (name "/CON1R4_N") (class "Default")
      (node (ref "J42") (pin "38") (pinfunction "38_38") (pintype "bidirectional"))
      (node (ref "R282") (pin "1") (pinfunction "1_1") (pintype "passive"))
    )
    (net (code "12") (name "/CON1R4_P") (class "Default")
      (node (ref "J42") (pin "4") (pinfunction "4_4") (pintype "bidirectional"))
      (node (ref "R281") (pin "2") (pinfunction "2_2") (pintype "passive"))
    )
    (net (code "13") (name "/CON1R5_N") (class "Default")
      (node (ref "J42") (pin "39") (pinfunction "39_39") (pintype "bidirectional"))
      (node (ref "R287") (pin "1") (pinfunction "1_1") (pintype "passive"))
    )
    (net (code "14") (name "/CON1R5_P") (class "Default")
      (node (ref "J42") (pin "5") (pinfunction "5_5") (pintype "bidirectional"))
      (node (ref "R286") (pin "2") (pinfunction "2_2") (pintype "passive"))
    )
    (net (code "16") (name "/CON1_N1") (class "Default")
      (node (ref "R267") (pin "2") (pinfunction "2_2") (pintype "passive"))
      (node (ref "R268") (pin "1") (pinfunction "1_1") (pintype "passive"))
    )
    (net (code "17") (name "/CON1_N2") (class "Default")
      (node (ref "R272") (pin "2") (pinfunction "2_2") (pintype "passive"))
      (node (ref "R273") (pin "1") (pinfunction "1_1") (pintype "passive"))
    )
    (net (code "18") (name "/CON1_N3") (class "Default")
      (node (ref "R277") (pin "2") (pinfunction "2_2") (pintype "passive"))
      (node (ref "R278") (pin "1") (pinfunction "1_1") (pintype "passive"))
    )
    (net (code "19") (name "/CON1_N4") (class "Default")
      (node (ref "R282") (pin "2") (pinfunction "2_2") (pintype "passive"))
      (node (ref "R283") (pin "1") (pinfunction "1_1") (pintype "passive"))
    )
    (net (code "20") (name "/CON1_N5") (class "Default")
      (node (ref "R287") (pin "2") (pinfunction "2_2") (pintype "passive"))
      (node (ref "R288") (pin "1") (pinfunction "1_1") (pintype "passive"))
    )
    (net (code "21") (name "/CON1_N6") (class "Default")
      (node (ref "J42") (pin "40") (pinfunction "40_40") (pintype "bidirectional"))
    )
    (net (code "22") (name "/CON1_N7") (class "Default")
      (node (ref "J42") (pin "41") (pinfunction "41_41") (pintype "bidirectional"))
    )
    (net (code "23") (name "/CON1_N8") (class "Default")
      (node (ref "J42") (pin "42") (pinfunction "42_42") (pintype "bidirectional"))
    )
    (net (code "24") (name "/CON1_N9") (class "Default")
      (node (ref "J42") (pin "43") (pinfunction "43_43") (pintype "bidirectional"))
    )
    (net (code "25") (name "/CON1_N10") (class "Default")
      (node (ref "J42") (pin "44") (pinfunction "44_44") (pintype "bidirectional"))
    )
    (net (code "26") (name "/CON1_N11") (class "Default")
      (node (ref "J42") (pin "45") (pinfunction "45_45") (pintype "bidirectional"))
    )
    (net (code "27") (name "/CON1_N12") (class "Default")
      (node (ref "J42") (pin "46") (pinfunction "46_46") (pintype "bidirectional"))
    )
    (net (code "28") (name "/CON1_N13") (class "Default")
      (node (ref "J42") (pin "47") (pinfunction "47_47") (pintype "bidirectional"))
    )
    (net (code "29") (name "/CON1_N14") (class "Default")
      (node (ref "J42") (pin "48") (pinfunction "48_48") (pintype "bidirectional"))
    )
    (net (code "30") (name "/CON1_N15") (class "Default")
      (node (ref "J42") (pin "49") (pinfunction "49_49") (pintype "bidirectional"))
    )
    (net (code "31") (name "/CON1_N16") (class "Default")
      (node (ref "J42") (pin "50") (pinfunction "50_50") (pintype "bidirectional"))
    )
    (net (code "32") (name "/CON1_N17") (class "Default")
      (node (ref "J42") (pin "53") (pinfunction "53_53") (pintype "bidirectional"))
    )
    (net (code "33") (name "/CON1_N18") (class "Default")
      (node (ref "J42") (pin "54") (pinfunction "54_54") (pintype "bidirectional"))
    )
    (net (code "34") (name "/CON1_N19") (class "Default")
      (node (ref "J42") (pin "55") (pinfunction "55_55") (pintype "bidirectional"))
    )
    (net (code "35") (name "/CON1_N20") (class "Default")
      (node (ref "J42") (pin "56") (pinfunction "56_56") (pintype "bidirectional"))
    )
    (net (code "36") (name "/CON1_N21") (class "Default")
      (node (ref "J42") (pin "57") (pinfunction "57_57") (pintype "bidirectional"))
    )
    (net (code "37") (name "/CON1_N22") (class "Default")
      (node (ref "J42") (pin "58") (pinfunction "58_58") (pintype "bidirectional"))
    )
    (net (code "38") (name "/CON1_N23") (class "Default")
      (node (ref "J42") (pin "59") (pinfunction "59_59") (pintype "bidirectional"))
    )
    (net (code "39") (name "/CON1_N24") (class "Default")
      (node (ref "J42") (pin "60") (pinfunction "60_60") (pintype "bidirectional"))
    )
    (net (code "40") (name "/CON1_N25") (class "Default")
      (node (ref "J42") (pin "61") (pinfunction "61_61") (pintype "bidirectional"))
    )
    (net (code "41") (name "/CON1_N26") (class "Default")
      (node (ref "J42") (pin "62") (pinfunction "62_62") (pintype "bidirectional"))
    )
    (net (code "42") (name "/CON1_N27") (class "Default")
      (node (ref "J42") (pin "63") (pinfunction "63_63") (pintype "bidirectional"))
    )
    (net (code "43") (name "/CON1_N28") (class "Default")
      (node (ref "J42") (pin "64") (pinfunction "64_64") (pintype "bidirectional"))
    )
    (net (code "44") (name "/CON1_N29") (class "Default")
      (node (ref "J42") (pin "65") (pinfunction "65_65") (pintype "bidirectional"))
    )
    (net (code "45") (name "/CON1_N30") (class "Default")
      (node (ref "J42") (pin "66") (pinfunction "66_66") (pintype "bidirectional"))
    )
    (net (code "46") (name "/CON1_N31") (class "Default")
      (node (ref "J42") (pin "67") (pinfunction "67_67") (pintype "bidirectional"))
    )
    (net (code "47") (name "/CON1_N32") (class "Default")
      (node (ref "J42") (pin "68") (pinfunction "68_68") (pintype "bidirectional"))
    )
    (net (code "50") (name "/CON1_P1") (class "Default")
      (node (ref "R265") (pin "2") (pinfunction "2_2") (pintype "passive"))
      (node (ref "R266") (pin "1") (pinfunction "1_1") (pintype "passive"))
    )
    (net (code "51") (name "/CON1_P2") (class "Default")
      (node (ref "R270") (pin "2") (pinfunction "2_2") (pintype "passive"))
      (node (ref "R271") (pin "1") (pinfunction "1_1") (pintype "passive"))
    )
    (net (code "52") (name "/CON1_P3") (class "Default")
      (node (ref "R275") (pin "2") (pinfunction "2_2") (pintype "passive"))
      (node (ref "R276") (pin "1") (pinfunction "1_1") (pintype "passive"))
    )
    (net (code "53") (name "/CON1_P4") (class "Default")
      (node (ref "R280") (pin "2") (pinfunction "2_2") (pintype "passive"))
      (node (ref "R281") (pin "1") (pinfunction "1_1") (pintype "passive"))
    )
    (net (code "54") (name "/CON1_P5") (class "Default")
      (node (ref "R285") (pin "2") (pinfunction "2_2") (pintype "passive"))
      (node (ref "R286") (pin "1") (pinfunction "1_1") (pintype "passive"))
    )
    (net (code "55") (name "/CON1_P6") (class "Default")
      (node (ref "J42") (pin "6") (pinfunction "6_6") (pintype "bidirectional"))
    )
    (net (code "56") (name "/CON1_P7") (class "Default")
      (node (ref "J42") (pin "7") (pinfunction "7_7") (pintype "bidirectional"))
    )
    (net (code "57") (name "/CON1_P8") (class "Default")
      (node (ref "J42") (pin "8") (pinfunction "8_8") (pintype "bidirectional"))
    )
    (net (code "58") (name "/CON1_P9") (class "Default")
      (node (ref "J42") (pin "9") (pinfunction "9_9") (pintype "bidirectional"))
    )
    (net (code "59") (name "/CON1_P10") (class "Default")
      (node (ref "J42") (pin "10") (pinfunction "10_10") (pintype "bidirectional"))
    )
    (net (code "60") (name "/CON1_P11") (class "Default")
      (node (ref "J42") (pin "11") (pinfunction "11_11") (pintype "bidirectional"))
    )
    (net (code "61") (name "/CON1_P12") (class "Default")
      (node (ref "J42") (pin "12") (pinfunction "12_12") (pintype "bidirectional"))
    )
    (net (code "62") (name "/CON1_P13") (class "Default")
      (node (ref "J42") (pin "13") (pinfunction "13_13") (pintype "bidirectional"))
    )
    (net (code "63") (name "/CON1_P14") (class "Default")
      (node (ref "J42") (pin "14") (pinfunction "14_14") (pintype "bidirectional"))
    )
    (net (code "64") (name "/CON1_P15") (class "Default")
      (node (ref "J42") (pin "15") (pinfunction "15_15") (pintype "bidirectional"))
    )
    (net (code "65") (name "/CON1_P16") (class "Default")
      (node (ref "J42") (pin "16") (pinfunction "16_16") (pintype "bidirectional"))
    )
    (net (code "66") (name "/CON1_P17") (class "Default")
      (node (ref "J42") (pin "19") (pinfunction "19_19") (pintype "bidirectional"))
    )
    (net (code "67") (name "/CON1_P18") (class "Default")
      (node (ref "J42") (pin "20") (pinfunction "20_20") (pintype "bidirectional"))
    )
    (net (code "68") (name "/CON1_P19") (class "Default")
      (node (ref "J42") (pin "21") (pinfunction "21_21") (pintype "bidirectional"))
    )
    (net (code "69") (name "/CON1_P20") (class "Default")
      (node (ref "J42") (pin "22") (pinfunction "22_22") (pintype "bidirectional"))
    )
    (net (code "70") (name "/CON1_P21") (class "Default")
      (node (ref "J42") (pin "23") (pinfunction "23_23") (pintype "bidirectional"))
    )
    (net (code "71") (name "/CON1_P22") (class "Default")
      (node (ref "J42") (pin "24") (pinfunction "24_24") (pintype "bidirectional"))
    )
    (net (code "72") (name "/CON1_P23") (class "Default")
      (node (ref "J42") (pin "25") (pinfunction "25_25") (pintype "bidirectional"))
    )
    (net (code "73") (name "/CON1_P24") (class "Default")
      (node (ref "J42") (pin "26") (pinfunction "26_26") (pintype "bidirectional"))
    )
    (net (code "74") (name "/CON1_P25") (class "Default")
      (node (ref "J42") (pin "27") (pinfunction "27_27") (pintype "bidirectional"))
    )
    (net (code "75") (name "/CON1_P26") (class "Default")
      (node (ref "J42") (pin "28") (pinfunction "28_28") (pintype "bidirectional"))
    )
    (net (code "76") (name "/CON1_P27") (class "Default")
      (node (ref "J42") (pin "29") (pinfunction "29_29") (pintype "bidirectional"))
    )
    (net (code "77") (name "/CON1_P28") (class "Default")
      (node (ref "J42") (pin "30") (pinfunction "30_30") (pintype "bidirectional"))
    )
    (net (code "78") (name "/CON1_P29") (class "Default")
      (node (ref "J42") (pin "31") (pinfunction "31_31") (pintype "bidirectional"))
    )
    (net (code "79") (name "/CON1_P30") (class "Default")
      (node (ref "J42") (pin "32") (pinfunction "32_32") (pintype "bidirectional"))
    )
    (net (code "80") (name "/CON1_P31") (class "Default")
      (node (ref "J42") (pin "33") (pinfunction "33_33") (pintype "bidirectional"))
    )
    (net (code "81") (name "/CON1_P32") (class "Default")
      (node (ref "J42") (pin "34") (pinfunction "34_34") (pintype "bidirectional"))
    )
    (net (code "83") (name "/DATA0_N") (class "Default")
      (node (ref "J41") (pin "11") (pinfunction "11_11") (pintype "bidirectional"))
      (node (ref "R285") (pin "1") (pinfunction "1_1") (pintype "passive"))
    )
    (net (code "84") (name "/DATA0_P") (class "Default")
      (node (ref "J41") (pin "9") (pinfunction "9_9") (pintype "bidirectional"))
      (node (ref "R288") (pin "2") (pinfunction "2_2") (pintype "passive"))
    )
    (net (code "85") (name "/DATA1_N") (class "Default")
      (node (ref "J41") (pin "8") (pinfunction "8_8") (pintype "bidirectional"))
      (node (ref "R280") (pin "1") (pinfunction "1_1") (pintype "passive"))
    )
    (net (code "86") (name "/DATA1_P") (class "Default")
      (node (ref "J41") (pin "6") (pinfunction "6_6") (pintype "bidirectional"))
      (node (ref "R283") (pin "2") (pinfunction "2_2") (pintype "passive"))
    )
    (net (code "87") (name "/DATA2_N") (class "Default")
      (node (ref "J41") (pin "5") (pinfunction "5_5") (pintype "bidirectional"))
      (node (ref "R275") (pin "1") (pinfunction "1_1") (pintype "passive"))
    )
    (net (code "88") (name "/DATA2_P") (class "Default")
      (node (ref "J41") (pin "3") (pinfunction "3_3") (pintype "bidirectional"))
      (node (ref "R278") (pin "2") (pinfunction "2_2") (pintype "passive"))
    )
    (net (code "90") (name "/EN1_RX1") (class "Default")
      (node (ref "IC56") (pin "1") (pinfunction "QB_1") (pintype "tri_state"))
      (node (ref "R257") (pin "1") (pinfunction "1_1") (pintype "passive"))
    )
    (net (code "91") (name "/EN1_RX2") (class "Default")
      (node (ref "IC56") (pin "15") (pinfunction "QA_15") (pintype "tri_state"))
      (node (ref "R256") (pin "1") (pinfunction "1_1") (pintype "passive"))
    )
    (net (code "92") (name "/EN1_RX3") (class "Default")
      (node (ref "IC56") (pin "3") (pinfunction "QD_3") (pintype "tri_state"))
      (node (ref "R259") (pin "1") (pinfunction "1_1") (pintype "passive"))
    )
    (net (code "93") (name "/EN1_RX4") (class "Default")
      (node (ref "IC56") (pin "2") (pinfunction "QC_2") (pintype "tri_state"))
      (node (ref "R258") (pin "1") (pinfunction "1_1") (pintype "passive"))
    )
    (net (code "94") (name "/EN1_RX5") (class "Default")
      (node (ref "IC56") (pin "5") (pinfunction "QF_5") (pintype "tri_state"))
      (node (ref "R261") (pin "1") (pinfunction "1_1") (pintype "passive"))
    )
    (net (code "95") (name "/EN1_RX6") (class "Default")
      (node (ref "IC56") (pin "4") (pinfunction "QE_4") (pintype "tri_state"))
      (node (ref "R260") (pin "1") (pinfunction "1_1") (pintype "passive"))
    )
    (net (code "96") (name "/EN1_RX7") (class "Default")
      (node (ref "IC56") (pin "7") (pinfunction "QH_7") (pintype "tri_state"))
      (node (ref "R263") (pin "1") (pinfunction "1_1") (pintype "passive"))
    )
    (net (code "97") (name "/EN1_RX8") (class "Default")
      (node (ref "IC56") (pin "6") (pinfunction "QG_6") (pintype "tri_state"))
      (node (ref "R262") (pin "1") (pinfunction "1_1") (pintype "passive"))
    )
    (net (code "98") (name "/EN1_RX9") (class "Default")
      (node (ref "IC57") (pin "1") (pinfunction "QB_1") (pintype "tri_state"))
      (node (ref "R269") (pin "1") (pinfunction "1_1") (pintype "passive"))
    )
    (net (code "99") (name "/EN1_RX10") (class "Default")
      (node (ref "IC57") (pin "15") (pinfunction "QA_15") (pintype "tri_state"))
      (node (ref "R264") (pin "1") (pinfunction "1_1") (pintype "passive"))
    )
    (net (code "100") (name "/EN1_RX11") (class "Default")
      (node (ref "IC57") (pin "3") (pinfunction "QD_3") (pintype "tri_state"))
      (node (ref "R279") (pin "1") (pinfunction "1_1") (pintype "passive"))
    )
    (net (code "101") (name "/EN1_RX12") (class "Default")
      (node (ref "IC57") (pin "2") (pinfunction "QC_2") (pintype "tri_state"))
      (node (ref "R274") (pin "1") (pinfunction "1_1") (pintype "passive"))
    )
    (net (code "102") (name "/EN1_RX13") (class "Default")
      (node (ref "IC57") (pin "5") (pinfunction "QF_5") (pintype "tri_state"))
      (node (ref "R289") (pin "1") (pinfunction "1_1") (pintype "passive"))
    )
    (net (code "103") (name "/EN1_RX14") (class "Default")
      (node (ref "IC57") (pin "4") (pinfunction "QE_4") (pintype "tri_state"))
      (node (ref "R284") (pin "1") (pinfunction "1_1") (pintype "passive"))
    )
    (net (code "104") (name "/EN1_RX15") (class "Default")
      (node (ref "IC57") (pin "7") (pinfunction "QH_7") (pintype "tri_state"))
      (node (ref "R291") (pin "1") (pinfunction "1_1") (pintype "passive"))
    )
    (net (code "105") (name "/EN1_RX16") (class "Default")
      (node (ref "IC57") (pin "6") (pinfunction "QG_6") (pintype "tri_state"))
      (node (ref "R290") (pin "1") (pinfunction "1_1") (pintype "passive"))
    )
    (net (code "106") (name "/EN1_RX17") (class "Default")
      (node (ref "IC58") (pin "1") (pinfunction "QB_1") (pintype "tri_state"))
      (node (ref "R293") (pin "1") (pinfunction "1_1") (pintype "passive"))
    )
    (net (code "107") (name "/EN1_RX18") (class "Default")
      (node (ref "IC58") (pin "15") (pinfunction "QA_15") (pintype "tri_state"))
      (node (ref "R292") (pin "1") (pinfunction "1_1") (pintype "passive"))
    )
    (net (code "108") (name "/EN1_RX19") (class "Default")
      (node (ref "IC58") (pin "3") (pinfunction "QD_3") (pintype "tri_state"))
      (node (ref "R295") (pin "1") (pinfunction "1_1") (pintype "passive"))
    )
    (net (code "109") (name "/EN1_RX20") (class "Default")
      (node (ref "IC58") (pin "2") (pinfunction "QC_2") (pintype "tri_state"))
      (node (ref "R294") (pin "1") (pinfunction "1_1") (pintype "passive"))
    )
    (net (code "110") (name "/EN1_RX21") (class "Default")
      (node (ref "IC58") (pin "5") (pinfunction "QF_5") (pintype "tri_state"))
      (node (ref "R297") (pin "1") (pinfunction "1_1") (pintype "passive"))
    )
    (net (code "111") (name "/EN1_RX22") (class "Default")
      (node (ref "IC58") (pin "4") (pinfunction "QE_4") (pintype "tri_state"))
      (node (ref "R296") (pin "1") (pinfunction "1_1") (pintype "passive"))
    )
    (net (code "112") (name "/EN1_RX23") (class "Default")
      (node (ref "IC58") (pin "7") (pinfunction "QH_7") (pintype "tri_state"))
      (node (ref "R299") (pin "1") (pinfunction "1_1") (pintype "passive"))
    )
    (net (code "113") (name "/EN1_RX24") (class "Default")
      (node (ref "IC58") (pin "6") (pinfunction "QG_6") (pintype "tri_state"))
      (node (ref "R298") (pin "1") (pinfunction "1_1") (pintype "passive"))
    )
    (net (code "114") (name "/EN1_RX25") (class "Default")
      (node (ref "IC59") (pin "1") (pinfunction "QB_1") (pintype "tri_state"))
      (node (ref "R301") (pin "1") (pinfunction "1_1") (pintype "passive"))
    )
    (net (code "115") (name "/EN1_RX26") (class "Default")
      (node (ref "IC59") (pin "15") (pinfunction "QA_15") (pintype "tri_state"))
      (node (ref "R300") (pin "1") (pinfunction "1_1") (pintype "passive"))
    )
    (net (code "116") (name "/EN1_RX27") (class "Default")
      (node (ref "IC59") (pin "3") (pinfunction "QD_3") (pintype "tri_state"))
      (node (ref "R303") (pin "1") (pinfunction "1_1") (pintype "passive"))
    )
    (net (code "117") (name "/EN1_RX28") (class "Default")
      (node (ref "IC59") (pin "2") (pinfunction "QC_2") (pintype "tri_state"))
      (node (ref "R302") (pin "1") (pinfunction "1_1") (pintype "passive"))
    )
    (net (code "118") (name "/EN1_RX29") (class "Default")
      (node (ref "IC59") (pin "5") (pinfunction "QF_5") (pintype "tri_state"))
      (node (ref "R305") (pin "1") (pinfunction "1_1") (pintype "passive"))
    )
    (net (code "119") (name "/EN1_RX30") (class "Default")
      (node (ref "IC59") (pin "4") (pinfunction "QE_4") (pintype "tri_state"))
      (node (ref "R304") (pin "1") (pinfunction "1_1") (pintype "passive"))
    )
    (net (code "120") (name "/EN1_RX31") (class "Default")
      (node (ref "IC59") (pin "7") (pinfunction "QH_7") (pintype "tri_state"))
      (node (ref "R307") (pin "1") (pinfunction "1_1") (pintype "passive"))
    )
    (net (code "121") (name "/EN1_RX32") (class "Default")
      (node (ref "IC59") (pin "6") (pinfunction "QG_6") (pintype "tri_state"))
      (node (ref "R306") (pin "1") (pinfunction "1_1") (pintype "passive"))
    )
    (net (code "193") (name "/HEAC_N") (class "Default")
      (node (ref "J41") (pin "1") (pinfunction "1_1") (pintype "bidirectional"))
      (node (ref "R265") (pin "1") (pinfunction "1_1") (pintype "passive"))
    )
    (net (code "194") (name "/HEAC_P") (class "Default")
      (node (ref "J41") (pin "2") (pinfunction "2_2") (pintype "bidirectional"))
      (node (ref "R268") (pin "2") (pinfunction "2_2") (pintype "passive"))
    )
    (net (code "195") (name "/LATCH") (class "Default")
      (node (ref "IC1") (pin "10") (pinfunction "B1_10") (pintype "bidirectional"))
      (node (ref "IC56") (pin "12") (pinfunction "RCLK_12") (pintype "input"))
      (node (ref "IC57") (pin "12") (pinfunction "RCLK_12") (pintype "input"))
      (node (ref "IC58") (pin "12") (pinfunction "RCLK_12") (pintype "input"))
      (node (ref "IC59") (pin "12") (pinfunction "RCLK_12") (pintype "input"))
    )
    (net (code "196") (name "/LATCH_VADJ") (class "Default")
      (node (ref "IC1") (pin "2") (pinfunction "A1_2") (pintype "bidirectional"))
      (node (ref "R2") (pin "2") (pinfunction "2_2") (pintype "passive"))
    )
    (net (code "198") (name "/REFIN") (class "Default")
      (node (ref "C149") (pin "2") (pinfunction "2_2") (pintype "passive"))
      (node (ref "IC55") (pin "1") (pinfunction "REFIN_1") (pintype "input"))
      (node (ref "R251") (pin "2") (pinfunction "2_2") (pintype "passive"))
      (node (ref "R253") (pin "2") (pinfunction "2_2") (pintype "passive"))
    )
    (net (code "199") (name "/SCL") (class "Default")
      (node (ref "IC60") (pin "3") (pinfunction "SCLIN_3") (pintype "bidirectional"))
    )
    (net (code "200") (name "/SCL_OUT") (class "Default")
      (node (ref "IC60") (pin "2") (pinfunction "SCLOUT_2") (pintype "bidirectional"))
      (node (ref "J41") (pin "17") (pinfunction "17_17") (pintype "bidirectional"))
      (node (ref "J42") (pin "17") (pinfunction "17_17") (pintype "bidirectional"))
      (node (ref "R311") (pin "1") (pinfunction "1_1") (pintype "passive"))
    )
    (net (code "201") (name "/SDA") (class "Default")
      (node (ref "IC60") (pin "6") (pinfunction "SDAIN_6") (pintype "bidirectional"))
    )
    (net (code "202") (name "/SDA_OUT") (class "Default")
      (node (ref "IC60") (pin "7") (pinfunction "SDAOUT_7") (pintype "bidirectional"))
      (node (ref "J41") (pin "18") (pinfunction "18_18") (pintype "bidirectional"))
      (node (ref "J42") (pin "51") (pinfunction "51_51") (pintype "bidirectional"))
      (node (ref "R310") (pin "1") (pinfunction "1_1") (pintype "passive"))
    )
    (net (code "203") (name "/SER_IN") (class "Default")
      (node (ref "IC1") (pin "8") (pinfunction "B3_8") (pintype "bidirectional"))
      (node (ref "IC56") (pin "14") (pinfunction "SER_14") (pintype "input"))
    )
    (net (code "204") (name "/SER_IN_VADJ") (class "Default")
      (node (ref "IC1") (pin "4") (pinfunction "A3_4") (pintype "bidirectional"))
    )
    (net (code "205") (name "/SER_OUT") (class "Default")
      (node (ref "IC1") (pin "7") (pinfunction "B4_7") (pintype "bidirectional"))
      (node (ref "IC59") (pin "9") (pinfunction "QH'_9") (pintype "output"))
    )
    (net (code "206") (name "/SER_OUT_VADJ") (class "Default")
      (node (ref "IC1") (pin "5") (pinfunction "A4_5") (pintype "bidirectional"))
    )
    (net (code "207") (name "/SUP") (class "Default")
      (node (ref "F7") (pin "1") (pinfunction "1_1") (pintype "passive"))
      (node (ref "J42") (pin "18") (pinfunction "18_18") (pintype "bidirectional"))
      (node (ref "J42") (pin "52") (pinfunction "52_52") (pintype "bidirectional"))
    )
    (net (code "208") (name "/VOSNS") (class "Default")
      (node (ref "C150") (pin "1") (pinfunction "1_1") (pintype "passive"))
      (node (ref "IC55") (pin "5") (pinfunction "VOSNS_5") (pintype "input"))
      (node (ref "R252") (pin "2") (pinfunction "2_2") (pintype "passive"))
    )
    (net (code "209") (name "3P3VAUX") (class "Default")
      (node (ref "C164") (pin "2") (pinfunction "2_2") (pintype "passive"))
      (node (ref "IC60") (pin "8") (pinfunction "Vcc_8") (pintype "power_in"))
      (node (ref "R310") (pin "2") (pinfunction "2_2") (pintype "passive"))
      (node (ref "R311") (pin "2") (pinfunction "2_2") (pintype "passive"))
      (node (ref "R312") (pin "2") (pinfunction "2_2") (pintype "passive"))
    )
    (net (code "210") (name "GND") (class "Default")
      (node (ref "B10") (pin "1") (pinfunction "1_1") (pintype "bidirectional"))
      (node (ref "B11") (pin "1") (pinfunction "1_1") (pintype "bidirectional"))
      (node (ref "B8") (pin "1") (pinfunction "1_1") (pintype "bidirectional"))
      (node (ref "B9") (pin "1") (pinfunction "1_1") (pintype "bidirectional"))
      (node (ref "C1") (pin "2") (pinfunction "2_2") (pintype "passive"))
      (node (ref "C146") (pin "1") (pinfunction "1_1") (pintype "passive"))
      (node (ref "C147") (pin "1") (pinfunction "1_1") (pintype "passive"))
      (node (ref "C148") (pin "1") (pinfunction "1_1") (pintype "passive"))
      (node (ref "C149") (pin "1") (pinfunction "1_1") (pintype "passive"))
      (node (ref "C150") (pin "2") (pinfunction "2_2") (pintype "passive"))
      (node (ref "C151") (pin "1") (pinfunction "1_1") (pintype "passive"))
      (node (ref "C152") (pin "1") (pinfunction "1_1") (pintype "passive"))
      (node (ref "C153") (pin "1") (pinfunction "1_1") (pintype "passive"))
      (node (ref "C154") (pin "1") (pinfunction "1_1") (pintype "passive"))
      (node (ref "C155") (pin "1") (pinfunction "1_1") (pintype "passive"))
      (node (ref "C156") (pin "1") (pinfunction "1_1") (pintype "passive"))
      (node (ref "C157") (pin "2") (pinfunction "2_2") (pintype "passive"))
      (node (ref "C158") (pin "2") (pinfunction "2_2") (pintype "passive"))
      (node (ref "C159") (pin "2") (pinfunction "2_2") (pintype "passive"))
      (node (ref "C160") (pin "2") (pinfunction "2_2") (pintype "passive"))
      (node (ref "C161") (pin "2") (pinfunction "2_2") (pintype "passive"))
      (node (ref "C162") (pin "2") (pinfunction "2_2") (pintype "passive"))
      (node (ref "C163") (pin "1") (pinfunction "1_1") (pintype "passive"))
      (node (ref "C164") (pin "1") (pinfunction "1_1") (pintype "passive"))
      (node (ref "C2") (pin "2") (pinfunction "2_2") (pintype "passive"))
      (node (ref "IC1") (pin "6") (pinfunction "GND_6") (pintype "power_in"))
      (node (ref "IC55") (pin "11") (pinfunction "EP_11") (pintype "power_in"))
      (node (ref "IC55") (pin "4") (pinfunction "PGND_4") (pintype "power_in"))
      (node (ref "IC55") (pin "8") (pinfunction "GND_8") (pintype "power_in"))
      (node (ref "IC56") (pin "13") (pinfunction "~{OE}_13") (pintype "input"))
      (node (ref "IC56") (pin "8") (pinfunction "GND_8") (pintype "power_in"))
      (node (ref "IC57") (pin "13") (pinfunction "~{OE}_13") (pintype "input"))
      (node (ref "IC57") (pin "8") (pinfunction "GND_8") (pintype "power_in"))
      (node (ref "IC58") (pin "13") (pinfunction "~{OE}_13") (pintype "input"))
      (node (ref "IC58") (pin "8") (pinfunction "GND_8") (pintype "power_in"))
      (node (ref "IC59") (pin "13") (pinfunction "~{OE}_13") (pintype "input"))
      (node (ref "IC59") (pin "8") (pinfunction "GND_8") (pintype "power_in"))
      (node (ref "IC60") (pin "4") (pinfunction "GND_4") (pintype "power_in"))
      (node (ref "J41") (pin "10") (pinfunction "10_10") (pintype "bidirectional"))
      (node (ref "J41") (pin "13") (pinfunction "13_13") (pintype "bidirectional"))
      (node (ref "J41") (pin "16") (pinfunction "16_16") (pintype "bidirectional"))
      (node (ref "J41") (pin "4") (pinfunction "4_4") (pintype "bidirectional"))
      (node (ref "J41") (pin "7") (pinfunction "7_7") (pintype "bidirectional"))
      (node (ref "J41") (pin "SHIELD") (pinfunction "SHIELD_SHIELD") (pintype "power_in"))
      (node (ref "J42") (pin "69") (pinfunction "69_69") (pintype "passive"))
      (node (ref "J42") (pin "70") (pinfunction "70_70") (pintype "passive"))
      (node (ref "R2") (pin "1") (pinfunction "1_1") (pintype "passive"))
      (node (ref "R253") (pin "1") (pinfunction "1_1") (pintype "passive"))
      (node (ref "R255") (pin "1") (pinfunction "1_1") (pintype "passive"))
      (node (ref "R256") (pin "2") (pinfunction "2_2") (pintype "passive"))
      (node (ref "R257") (pin "2") (pinfunction "2_2") (pintype "passive"))
      (node (ref "R258") (pin "2") (pinfunction "2_2") (pintype "passive"))
      (node (ref "R259") (pin "2") (pinfunction "2_2") (pintype "passive"))
      (node (ref "R260") (pin "2") (pinfunction "2_2") (pintype "passive"))
      (node (ref "R261") (pin "2") (pinfunction "2_2") (pintype "passive"))
      (node (ref "R262") (pin "2") (pinfunction "2_2") (pintype "passive"))
      (node (ref "R263") (pin "2") (pinfunction "2_2") (pintype "passive"))
      (node (ref "R264") (pin "2") (pinfunction "2_2") (pintype "passive"))
      (node (ref "R269") (pin "2") (pinfunction "2_2") (pintype "passive"))
      (node (ref "R274") (pin "2") (pinfunction "2_2") (pintype "passive"))
      (node (ref "R279") (pin "2") (pinfunction "2_2") (pintype "passive"))
      (node (ref "R284") (pin "2") (pinfunction "2_2") (pintype "passive"))
      (node (ref "R289") (pin "2") (pinfunction "2_2") (pintype "passive"))
      (node (ref "R290") (pin "2") (pinfunction "2_2") (pintype "passive"))
      (node (ref "R291") (pin "2") (pinfunction "2_2") (pintype "passive"))
      (node (ref "R292") (pin "2") (pinfunction "2_2") (pintype "passive"))
      (node (ref "R293") (pin "2") (pinfunction "2_2") (pintype "passive"))
      (node (ref "R294") (pin "2") (pinfunction "2_2") (pintype "passive"))
      (node (ref "R295") (pin "2") (pinfunction "2_2") (pintype "passive"))
      (node (ref "R296") (pin "2") (pinfunction "2_2") (pintype "passive"))
      (node (ref "R297") (pin "2") (pinfunction "2_2") (pintype "passive"))
      (node (ref "R298") (pin "2") (pinfunction "2_2") (pintype "passive"))
      (node (ref "R299") (pin "2") (pinfunction "2_2") (pintype "passive"))
      (node (ref "R300") (pin "2") (pinfunction "2_2") (pintype "passive"))
      (node (ref "R301") (pin "2") (pinfunction "2_2") (pintype "passive"))
      (node (ref "R302") (pin "2") (pinfunction "2_2") (pintype "passive"))
      (node (ref "R303") (pin "2") (pinfunction "2_2") (pintype "passive"))
      (node (ref "R304") (pin "2") (pinfunction "2_2") (pintype "passive"))
      (node (ref "R305") (pin "2") (pinfunction "2_2") (pintype "passive"))
      (node (ref "R306") (pin "2") (pinfunction "2_2") (pintype "passive"))
      (node (ref "R307") (pin "2") (pinfunction "2_2") (pintype "passive"))
      (node (ref "R308") (pin "2") (pinfunction "2_2") (pintype "passive"))
    )
    (net (code "211") (name "LVDS_REF") (class "Default")
      (node (ref "C147") (pin "2") (pinfunction "2_2") (pintype "passive"))
      (node (ref "C151") (pin "2") (pinfunction "2_2") (pintype "passive"))
      (node (ref "C152") (pin "2") (pinfunction "2_2") (pintype "passive"))
      (node (ref "IC55") (pin "3") (pinfunction "VO_3") (pintype "power_in"))
      (node (ref "IC55") (pin "6") (pinfunction "REFOUT_6") (pintype "output"))
      (node (ref "R252") (pin "1") (pinfunction "1_1") (pintype "passive"))
      (node (ref "R254") (pin "1") (pinfunction "1_1") (pintype "passive"))
      (node (ref "R255") (pin "2") (pinfunction "2_2") (pintype "passive"))
    )
    (net (code "212") (name "Net-(F6-Pad2)") (class "Default")
      (node (ref "F6") (pin "2") (pinfunction "2_2") (pintype "passive"))
      (node (ref "J41") (pin "19") (pinfunction "19_19") (pintype "bidirectional"))
    )
    (net (code "213") (name "Net-(IC56-QH')") (class "Default")
      (node (ref "IC56") (pin "9") (pinfunction "QH'_9") (pintype "output"))
      (node (ref "IC57") (pin "14") (pinfunction "SER_14") (pintype "input"))
    )
    (net (code "214") (name "Net-(IC57-QH')") (class "Default")
      (node (ref "IC57") (pin "9") (pinfunction "QH'_9") (pintype "output"))
      (node (ref "IC58") (pin "14") (pinfunction "SER_14") (pintype "input"))
    )
    (net (code "215") (name "Net-(IC58-QH')") (class "Default")
      (node (ref "IC58") (pin "9") (pinfunction "QH'_9") (pintype "output"))
      (node (ref "IC59") (pin "14") (pinfunction "SER_14") (pintype "input"))
    )
    (net (code "216") (name "Net-(IC60-EN)") (class "Default")
      (node (ref "C163") (pin "2") (pinfunction "2_2") (pintype "passive"))
      (node (ref "IC60") (pin "1") (pinfunction "EN_1") (pintype "input"))
      (node (ref "R309") (pin "2") (pinfunction "2_2") (pintype "passive"))
    )
    (net (code "217") (name "Net-(IC60-READY)") (class "Default")
      (node (ref "IC60") (pin "5") (pinfunction "READY_5") (pintype "output"))
      (node (ref "R312") (pin "1") (pinfunction "1_1") (pintype "passive"))
    )
    (net (code "218") (name "P3V3") (class "Default")
      (node (ref "C1") (pin "1") (pinfunction "1_1") (pintype "passive"))
      (node (ref "C146") (pin "2") (pinfunction "2_2") (pintype "passive"))
      (node (ref "C148") (pin "2") (pinfunction "2_2") (pintype "passive"))
      (node (ref "C153") (pin "2") (pinfunction "2_2") (pintype "passive"))
      (node (ref "C154") (pin "2") (pinfunction "2_2") (pintype "passive"))
      (node (ref "C155") (pin "2") (pinfunction "2_2") (pintype "passive"))
      (node (ref "C156") (pin "2") (pinfunction "2_2") (pintype "passive"))
      (node (ref "C157") (pin "1") (pinfunction "1_1") (pintype "passive"))
      (node (ref "C158") (pin "1") (pinfunction "1_1") (pintype "passive"))
      (node (ref "C159") (pin "1") (pinfunction "1_1") (pintype "passive"))
      (node (ref "C160") (pin "1") (pinfunction "1_1") (pintype "passive"))
      (node (ref "C161") (pin "1") (pinfunction "1_1") (pintype "passive"))
      (node (ref "C162") (pin "1") (pinfunction "1_1") (pintype "passive"))
      (node (ref "F6") (pin "1") (pinfunction "1_1") (pintype "passive"))
      (node (ref "F7") (pin "2") (pinfunction "2_2") (pintype "passive"))
      (node (ref "IC1") (pin "11") (pinfunction "VCCB_11") (pintype "power_in"))
      (node (ref "IC55") (pin "10") (pinfunction "VIN_10") (pintype "input"))
      (node (ref "IC55") (pin "2") (pinfunction "VLDOIN_2") (pintype "input"))
      (node (ref "IC55") (pin "7") (pinfunction "EN_7") (pintype "input"))
      (node (ref "IC56") (pin "10") (pinfunction "~{SRCLR}_10") (pintype "input"))
      (node (ref "IC56") (pin "16") (pinfunction "VCC_16") (pintype "power_in"))
      (node (ref "IC57") (pin "10") (pinfunction "~{SRCLR}_10") (pintype "input"))
      (node (ref "IC57") (pin "16") (pinfunction "VCC_16") (pintype "power_in"))
      (node (ref "IC58") (pin "10") (pinfunction "~{SRCLR}_10") (pintype "input"))
      (node (ref "IC58") (pin "16") (pinfunction "VCC_16") (pintype "power_in"))
      (node (ref "IC59") (pin "10") (pinfunction "~{SRCLR}_10") (pintype "input"))
      (node (ref "IC59") (pin "16") (pinfunction "VCC_16") (pintype "power_in"))
      (node (ref "R251") (pin "1") (pinfunction "1_1") (pintype "passive"))
      (node (ref "R254") (pin "2") (pinfunction "2_2") (pintype "passive"))
      (node (ref "R308") (pin "1") (pinfunction "1_1") (pintype "passive"))
      (node (ref "R309") (pin "1") (pinfunction "1_1") (pintype "passive"))
    )
    (net (code "219") (name "VADJ") (class "Default")
      (node (ref "C2") (pin "1") (pinfunction "1_1") (pintype "passive"))
      (node (ref "IC1") (pin "1") (pinfunction "VCCA_1") (pintype "power_in"))
      (node (ref "IC1") (pin "12") (pinfunction "OE_12") (pintype "input"))
    )
    (net (code "220") (name "unconnected-(IC55-PGOOD-Pad9)") (class "Default")
      (node (ref "IC55") (pin "9") (pinfunction "PGOOD_9") (pintype "output"))
    )
    (net (code "221") (name "unconnected-(J41-Pad15)") (class "Default")
      (node (ref "J41") (pin "15") (pinfunction "15_15") (pintype "bidirectional"))
    )
  )
)
